# ZOWI_Main_Board_Bluetooth.net
KiCad netlist of a schematic drawn in Altium Designer
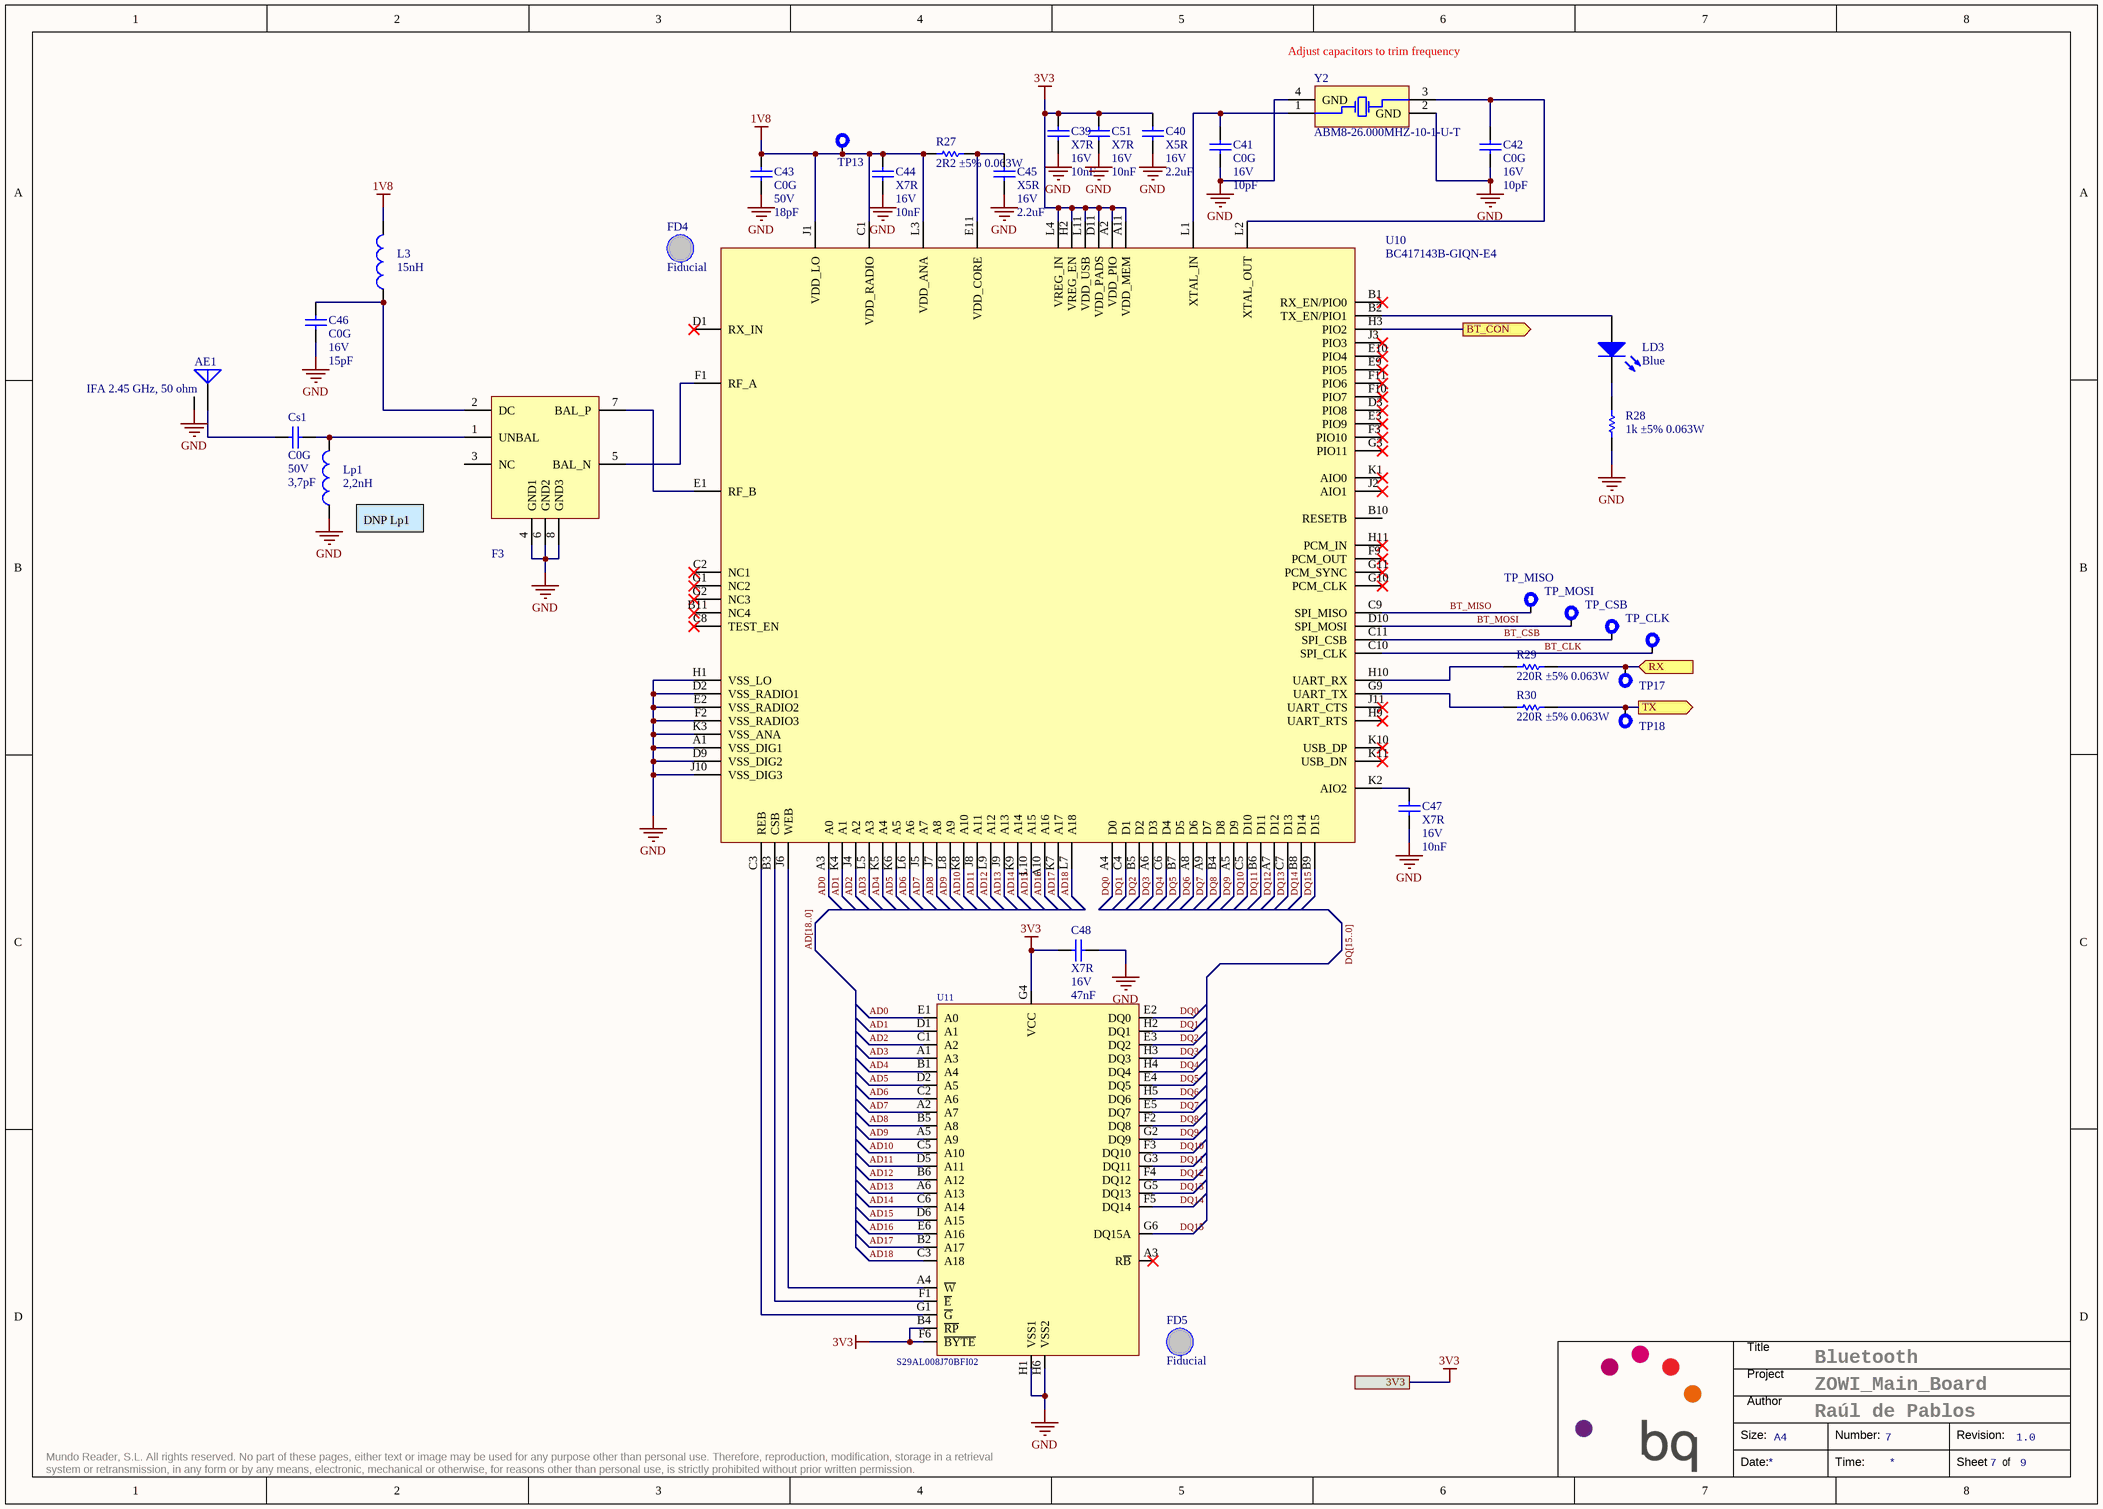
[diagram p0: ZOWI_Main_Board_Bluetooth.SchDoc]

(export (version "E")
  (design (tool "Eeschema 10.0.6"))
  (components
    (comp (ref "AE1")
      (value "~")
      (footprint "IFA_2,45GHZ_50OHM")
      (description "Antenna with Ground")
      (fields (field (name "PART NUMBER") "Microstrip_2.4GHz"))
      (libsource (lib "Antennas") (part "Antenna_WG"))
    )
    (comp (ref "C39")
      (value "Capacitor")
      (footprint "C0402")
      (description "Capacitor SMD")
      (fields
        (field (name "DIELECTRIC") "X7R")
        (field (name "VOLTAGE") "16V")
        (field (name "CAPACITANCE") "10nF")
        (field (name "PART NUMBER") "C0402_10nF_16V_±10%")
        (field (name "TOLERANCE") "±10%")
      )
      (libsource (lib "Pasives_Capacitor_SMD") (part "Capacitor"))
    )
    (comp (ref "C40")
      (value "Capacitor")
      (footprint "C0603")
      (description "Capacitor SMD")
      (fields
        (field (name "DIELECTRIC") "X5R")
        (field (name "VOLTAGE") "16V")
        (field (name "CAPACITANCE") "2.2uF")
        (field (name "PART NUMBER") "C0603_2.2uF_16V_±10%")
        (field (name "TOLERANCE") "±10%")
      )
      (libsource (lib "Pasives_Capacitor_SMD") (part "Capacitor"))
    )
    (comp (ref "C41")
      (value "Capacitor")
      (footprint "C0402")
      (description "Capacitor SMD")
      (fields
        (field (name "DIELECTRIC") "C0G")
        (field (name "VOLTAGE") "16V")
        (field (name "CAPACITANCE") "10pF")
        (field (name "PART NUMBER") "C0402_10pF_16V_±10%")
        (field (name "TOLERANCE") "±10%")
      )
      (libsource (lib "Pasives_Capacitor_SMD") (part "Capacitor"))
    )
    (comp (ref "C42")
      (value "Capacitor")
      (footprint "C0402")
      (description "Capacitor SMD")
      (fields
        (field (name "DIELECTRIC") "C0G")
        (field (name "VOLTAGE") "16V")
        (field (name "CAPACITANCE") "10pF")
        (field (name "PART NUMBER") "C0402_10pF_16V_±10%")
        (field (name "TOLERANCE") "±10%")
      )
      (libsource (lib "Pasives_Capacitor_SMD") (part "Capacitor"))
    )
    (comp (ref "C43")
      (value "Capacitor")
      (footprint "C0402")
      (description "Capacitor SMD")
      (fields
        (field (name "DIELECTRIC") "C0G")
        (field (name "VOLTAGE") "50V")
        (field (name "CAPACITANCE") "18pF")
        (field (name "PART NUMBER") "C0402_18pF_50V_±5%")
        (field (name "TOLERANCE") "±5%")
      )
      (libsource (lib "Pasives_Capacitor_SMD") (part "Capacitor"))
    )
    (comp (ref "C44")
      (value "Capacitor")
      (footprint "C0402")
      (description "Capacitor SMD")
      (fields
        (field (name "DIELECTRIC") "X7R")
        (field (name "VOLTAGE") "16V")
        (field (name "CAPACITANCE") "10nF")
        (field (name "PART NUMBER") "C0402_10nF_16V_±10%")
        (field (name "TOLERANCE") "±10%")
      )
      (libsource (lib "Pasives_Capacitor_SMD") (part "Capacitor"))
    )
    (comp (ref "C45")
      (value "Capacitor")
      (footprint "C0603")
      (description "Capacitor SMD")
      (fields
        (field (name "DIELECTRIC") "X5R")
        (field (name "VOLTAGE") "16V")
        (field (name "CAPACITANCE") "2.2uF")
        (field (name "PART NUMBER") "C0603_2.2uF_16V_±10%")
        (field (name "TOLERANCE") "±10%")
      )
      (libsource (lib "Pasives_Capacitor_SMD") (part "Capacitor"))
    )
    (comp (ref "C46")
      (value "Capacitor")
      (footprint "C0402")
      (description "Capacitor SMD")
      (fields
        (field (name "DIELECTRIC") "C0G")
        (field (name "VOLTAGE") "16V")
        (field (name "CAPACITANCE") "15pF")
        (field (name "PART NUMBER") "C0402_15pF_16V_±10%")
        (field (name "TOLERANCE") "±10%")
      )
      (libsource (lib "Pasives_Capacitor_SMD") (part "Capacitor"))
    )
    (comp (ref "C47")
      (value "Capacitor")
      (footprint "C0402")
      (description "Capacitor SMD")
      (fields
        (field (name "DIELECTRIC") "X7R")
        (field (name "VOLTAGE") "16V")
        (field (name "CAPACITANCE") "10nF")
        (field (name "PART NUMBER") "C0402_10nF_16V_±10%")
        (field (name "TOLERANCE") "±10%")
      )
      (libsource (lib "Pasives_Capacitor_SMD") (part "Capacitor"))
    )
    (comp (ref "C48")
      (value "Capacitor")
      (footprint "C0402")
      (description "Capacitor SMD")
      (fields
        (field (name "DIELECTRIC") "X7R")
        (field (name "VOLTAGE") "16V")
        (field (name "CAPACITANCE") "47nF")
        (field (name "PART NUMBER") "C0402_47nF_16V_±10%")
        (field (name "TOLERANCE") "±10%")
      )
      (libsource (lib "Pasives_Capacitor_SMD") (part "Capacitor"))
    )
    (comp (ref "C51")
      (value "Capacitor")
      (footprint "C0402")
      (description "Capacitor SMD")
      (fields
        (field (name "DIELECTRIC") "X7R")
        (field (name "VOLTAGE") "16V")
        (field (name "CAPACITANCE") "10nF")
        (field (name "PART NUMBER") "C0402_10nF_16V_±10%")
        (field (name "TOLERANCE") "±10%")
      )
      (libsource (lib "Pasives_Capacitor_SMD") (part "Capacitor"))
    )
    (comp (ref "Cs1")
      (value "Capacitor")
      (footprint "C0402")
      (description "Capacitor SMD")
      (fields
        (field (name "DIELECTRIC") "C0G")
        (field (name "VOLTAGE") "50V")
        (field (name "CAPACITANCE") "3,7pF")
        (field (name "PART NUMBER") "C0402_3,7pF_50V_±0.05pF")
        (field (name "TOLERANCE") "±7%")
      )
      (libsource (lib "Pasives_Capacitor_SMD") (part "Capacitor"))
    )
    (comp (ref "F3")
      (value "BP_Filter_Balun")
      (footprint "2450FB15K0005")
      (description "Filter, Band Pass, Balun")
      (fields (field (name "MANUFACTURER") "Johanson Technlogy"))
      (libsource (lib "Pasives_Filter") (part "BP_Filter_Balun"))
    )
    (comp (ref "FD4")
      (value "Fiducial")
      (footprint "Fiducial_Local_0.4mm")
      (description "Fiducial Mark")
      (fields (field (name "PART NUMBER") "Fiducial Local 0.4mm"))
      (libsource (lib "Miscelanea") (part "Fiducial"))
    )
    (comp (ref "FD5")
      (value "Fiducial")
      (footprint "Fiducial_Local_0.4mm")
      (description "Fiducial Mark")
      (fields (field (name "PART NUMBER") "Fiducial Local 0.4mm"))
      (libsource (lib "Miscelanea") (part "Fiducial"))
    )
    (comp (ref "L3")
      (value "~")
      (footprint "L0402")
      (description "Inductor SMD")
      (fields
        (field (name "PART NUMBER") "15nH_0,3A")
        (field (name "L") "15nH")
        (field (name "MANUFACTURER") "Murata")
      )
      (libsource (lib "Pasivos_Inductor_SMD") (part "Inductor"))
    )
    (comp (ref "LD3")
      (value "Blue")
      (footprint "LED0603")
      (description "LED")
      (fields (field (name "PART NUMBER") "LTST-C194TBKT") (field (name "MANUFACTURER") "Lite-On"))
      (libsource (lib "Optoelectronics") (part "LED"))
    )
    (comp (ref "Lp1")
      (value "~")
      (footprint "L0402")
      (description "Inductor SMD")
      (fields
        (field (name "PART NUMBER") "2,2nH_0,9A")
        (field (name "L") "2,2nH")
        (field (name "MANUFACTURER") "Murata")
      )
      (libsource (lib "Pasivos_Inductor_SMD") (part "Inductor"))
    )
    (comp (ref "R27")
      (value "2R2 ±5% 0.063W")
      (footprint "R0402")
      (description "Resistor, SMD")
      (fields (field (name "TOLERANCE") "±5%") (field (name "POWER") "0.063W"))
      (libsource (lib "Pasives_Resistor_SMD") (part "Resistor"))
    )
    (comp (ref "R28")
      (value "1k ±5% 0.063W")
      (footprint "R0402")
      (description "Resistor, SMD")
      (fields (field (name "TOLERANCE") "±5%") (field (name "POWER") "0.063W"))
      (libsource (lib "Pasives_Resistor_SMD") (part "Resistor"))
    )
    (comp (ref "R29")
      (value "220R ±5% 0.063W")
      (footprint "R0402")
      (description "Resistor, SMD")
      (fields (field (name "TOLERANCE") "±5%") (field (name "POWER") "0.063W"))
      (libsource (lib "Pasives_Resistor_SMD") (part "Resistor"))
    )
    (comp (ref "R30")
      (value "220R ±5% 0.063W")
      (footprint "R0402")
      (description "Resistor, SMD")
      (fields (field (name "TOLERANCE") "±5%") (field (name "POWER") "0.063W"))
      (libsource (lib "Pasives_Resistor_SMD") (part "Resistor"))
    )
    (comp (ref "TP13")
      (value "Testpoint")
      (footprint "TP_SMD_1mm")
      (fields (field (name "MANUFACTURER") "Oxley") (field (name "PART NUMBER") "TP_SMD_1mm"))
      (libsource (lib "Miscelanea") (part "Testpoint"))
    )
    (comp (ref "TP17")
      (value "Testpoint")
      (footprint "TP_SMD_1mm")
      (fields (field (name "MANUFACTURER") "Oxley") (field (name "PART NUMBER") "TP_SMD_1mm"))
      (libsource (lib "Miscelanea") (part "Testpoint"))
    )
    (comp (ref "TP18")
      (value "Testpoint")
      (footprint "TP_SMD_1mm")
      (fields (field (name "MANUFACTURER") "Oxley") (field (name "PART NUMBER") "TP_SMD_1mm"))
      (libsource (lib "Miscelanea") (part "Testpoint"))
    )
    (comp (ref "TP_CLK")
      (value "Testpoint")
      (footprint "TP_SMD_1mm")
      (fields (field (name "MANUFACTURER") "Oxley") (field (name "PART NUMBER") "TP_SMD_1mm"))
      (libsource (lib "Miscelanea") (part "Testpoint"))
    )
    (comp (ref "TP_CSB")
      (value "Testpoint")
      (footprint "TP_SMD_1mm")
      (fields (field (name "MANUFACTURER") "Oxley") (field (name "PART NUMBER") "TP_SMD_1mm"))
      (libsource (lib "Miscelanea") (part "Testpoint"))
    )
    (comp (ref "TP_MISO")
      (value "Testpoint")
      (footprint "TP_SMD_1mm")
      (fields (field (name "MANUFACTURER") "Oxley") (field (name "PART NUMBER") "TP_SMD_1mm"))
      (libsource (lib "Miscelanea") (part "Testpoint"))
    )
    (comp (ref "TP_MOSI")
      (value "Testpoint")
      (footprint "TP_SMD_1mm")
      (fields (field (name "MANUFACTURER") "Oxley") (field (name "PART NUMBER") "TP_SMD_1mm"))
      (libsource (lib "Miscelanea") (part "Testpoint"))
    )
    (comp (ref "U10")
      (value "BC417143B-GIQN-E4")
      (footprint "TFBGA96P8X8")
      (description "Bluetooth Modem, 2.4-GHz Bluetooth SoC")
      (fields (field (name "PART NUMBER") "BlueCore4-EXT") (field (name "MANUFACTURER") "CSR"))
      (libsource (lib "Transceiver") (part "BC417143B"))
    )
    (comp (ref "U11")
      (value "S29AL008J70BFI02")
      (footprint "TFBGA48P6X8")
      (description "Memory NOR Flash 8-Mbit 3 V supply")
      (fields (field (name "PART NUMBER") "M29W800DT") (field (name "MANUFACTURER") "Spansion"))
      (libsource (lib "Memory_NOR") (part "M29W800DT"))
    )
    (comp (ref "Y2")
      (value "ABM8-26.000MHZ-10-1-U-T")
      (footprint "XTAL 3.2x2.5")
      (description "Crystal 4 pin")
      (fields (field (name "PART NUMBER") "403C11A 26MHz") (field (name "TOLERANCE") "±10ppm"))
      (libsource (lib "Frequency") (part "Crystal 4 pin"))
    )
  )
  (nets
    (net (code "1") (name "/AD0") (class "Default")
      (node (ref "U10") (pin "A3") (pinfunction "A0_A3") (pintype "passive"))
      (node (ref "U11") (pin "E1") (pinfunction "A0_E1") (pintype "passive"))
    )
    (net (code "2") (name "/AD1") (class "Default")
      (node (ref "U10") (pin "K4") (pinfunction "A1_K4") (pintype "passive"))
      (node (ref "U11") (pin "D1") (pinfunction "A1_D1") (pintype "passive"))
    )
    (net (code "3") (name "/AD2") (class "Default")
      (node (ref "U10") (pin "J4") (pinfunction "A2_J4") (pintype "passive"))
      (node (ref "U11") (pin "C1") (pinfunction "A2_C1") (pintype "passive"))
    )
    (net (code "4") (name "/AD3") (class "Default")
      (node (ref "U10") (pin "L5") (pinfunction "A3_L5") (pintype "passive"))
      (node (ref "U11") (pin "A1") (pinfunction "A3_A1") (pintype "passive"))
    )
    (net (code "5") (name "/AD4") (class "Default")
      (node (ref "U10") (pin "K5") (pinfunction "A4_K5") (pintype "passive"))
      (node (ref "U11") (pin "B1") (pinfunction "A4_B1") (pintype "passive"))
    )
    (net (code "6") (name "/AD5") (class "Default")
      (node (ref "U10") (pin "K6") (pinfunction "A5_K6") (pintype "passive"))
      (node (ref "U11") (pin "D2") (pinfunction "A5_D2") (pintype "passive"))
    )
    (net (code "7") (name "/AD6") (class "Default")
      (node (ref "U10") (pin "L6") (pinfunction "A6_L6") (pintype "passive"))
      (node (ref "U11") (pin "C2") (pinfunction "A6_C2") (pintype "passive"))
    )
    (net (code "8") (name "/AD7") (class "Default")
      (node (ref "U10") (pin "J5") (pinfunction "A7_J5") (pintype "passive"))
      (node (ref "U11") (pin "A2") (pinfunction "A7_A2") (pintype "passive"))
    )
    (net (code "9") (name "/AD8") (class "Default")
      (node (ref "U10") (pin "J7") (pinfunction "A8_J7") (pintype "passive"))
      (node (ref "U11") (pin "B5") (pinfunction "A8_B5") (pintype "passive"))
    )
    (net (code "10") (name "/AD9") (class "Default")
      (node (ref "U10") (pin "L8") (pinfunction "A9_L8") (pintype "passive"))
      (node (ref "U11") (pin "A5") (pinfunction "A9_A5") (pintype "passive"))
    )
    (net (code "11") (name "/AD10") (class "Default")
      (node (ref "U10") (pin "K8") (pinfunction "A10_K8") (pintype "passive"))
      (node (ref "U11") (pin "C5") (pinfunction "A10_C5") (pintype "passive"))
    )
    (net (code "12") (name "/AD11") (class "Default")
      (node (ref "U10") (pin "J8") (pinfunction "A11_J8") (pintype "passive"))
      (node (ref "U11") (pin "D5") (pinfunction "A11_D5") (pintype "passive"))
    )
    (net (code "13") (name "/AD12") (class "Default")
      (node (ref "U10") (pin "L9") (pinfunction "A12_L9") (pintype "passive"))
      (node (ref "U11") (pin "B6") (pinfunction "A12_B6") (pintype "passive"))
    )
    (net (code "14") (name "/AD13") (class "Default")
      (node (ref "U10") (pin "J9") (pinfunction "A13_J9") (pintype "passive"))
      (node (ref "U11") (pin "A6") (pinfunction "A13_A6") (pintype "passive"))
    )
    (net (code "15") (name "/AD14") (class "Default")
      (node (ref "U10") (pin "K9") (pinfunction "A14_K9") (pintype "passive"))
      (node (ref "U11") (pin "C6") (pinfunction "A14_C6") (pintype "passive"))
    )
    (net (code "16") (name "/AD15") (class "Default")
      (node (ref "U10") (pin "L10") (pinfunction "A15_L10") (pintype "passive"))
      (node (ref "U11") (pin "D6") (pinfunction "A15_D6") (pintype "passive"))
    )
    (net (code "17") (name "/AD16") (class "Default")
      (node (ref "U10") (pin "A10") (pinfunction "A16_A10") (pintype "passive"))
      (node (ref "U11") (pin "E6") (pinfunction "A16_E6") (pintype "passive"))
    )
    (net (code "18") (name "/AD17") (class "Default")
      (node (ref "U10") (pin "K7") (pinfunction "A17_K7") (pintype "passive"))
      (node (ref "U11") (pin "B2") (pinfunction "A17_B2") (pintype "passive"))
    )
    (net (code "19") (name "/AD18") (class "Default")
      (node (ref "U10") (pin "L7") (pinfunction "A18_L7") (pintype "passive"))
      (node (ref "U11") (pin "C3") (pinfunction "A18_C3") (pintype "passive"))
    )
    (net (code "21") (name "/BT_CLK") (class "Default")
      (node (ref "TP_CLK") (pin "1") (pinfunction "1_1") (pintype "passive"))
      (node (ref "U10") (pin "C10") (pinfunction "SPI_CLK_C10") (pintype "passive"))
    )
    (net (code "22") (name "/BT_CON") (class "Default")
      (node (ref "U10") (pin "H3") (pinfunction "PIO2_H3") (pintype "passive"))
    )
    (net (code "23") (name "/BT_CSB") (class "Default")
      (node (ref "TP_CSB") (pin "1") (pinfunction "1_1") (pintype "passive"))
      (node (ref "U10") (pin "C11") (pinfunction "SPI_CSB_C11") (pintype "passive"))
    )
    (net (code "24") (name "/BT_MISO") (class "Default")
      (node (ref "TP_MISO") (pin "1") (pinfunction "1_1") (pintype "passive"))
      (node (ref "U10") (pin "C9") (pinfunction "SPI_MISO_C9") (pintype "passive"))
    )
    (net (code "25") (name "/BT_MOSI") (class "Default")
      (node (ref "TP_MOSI") (pin "1") (pinfunction "1_1") (pintype "passive"))
      (node (ref "U10") (pin "D10") (pinfunction "SPI_MOSI_D10") (pintype "passive"))
    )
    (net (code "26") (name "/DQ0") (class "Default")
      (node (ref "U10") (pin "A4") (pinfunction "D0_A4") (pintype "passive"))
      (node (ref "U11") (pin "E2") (pinfunction "DQ0_E2") (pintype "passive"))
    )
    (net (code "27") (name "/DQ1") (class "Default")
      (node (ref "U10") (pin "C4") (pinfunction "D1_C4") (pintype "passive"))
      (node (ref "U11") (pin "H2") (pinfunction "DQ1_H2") (pintype "passive"))
    )
    (net (code "28") (name "/DQ2") (class "Default")
      (node (ref "U10") (pin "B5") (pinfunction "D2_B5") (pintype "passive"))
      (node (ref "U11") (pin "E3") (pinfunction "DQ2_E3") (pintype "passive"))
    )
    (net (code "29") (name "/DQ3") (class "Default")
      (node (ref "U10") (pin "A6") (pinfunction "D3_A6") (pintype "passive"))
      (node (ref "U11") (pin "H3") (pinfunction "DQ3_H3") (pintype "passive"))
    )
    (net (code "30") (name "/DQ4") (class "Default")
      (node (ref "U10") (pin "C6") (pinfunction "D4_C6") (pintype "passive"))
      (node (ref "U11") (pin "H4") (pinfunction "DQ4_H4") (pintype "passive"))
    )
    (net (code "31") (name "/DQ5") (class "Default")
      (node (ref "U10") (pin "B7") (pinfunction "D5_B7") (pintype "passive"))
      (node (ref "U11") (pin "E4") (pinfunction "DQ5_E4") (pintype "passive"))
    )
    (net (code "32") (name "/DQ6") (class "Default")
      (node (ref "U10") (pin "A8") (pinfunction "D6_A8") (pintype "passive"))
      (node (ref "U11") (pin "H5") (pinfunction "DQ6_H5") (pintype "passive"))
    )
    (net (code "33") (name "/DQ7") (class "Default")
      (node (ref "U10") (pin "A9") (pinfunction "D7_A9") (pintype "passive"))
      (node (ref "U11") (pin "E5") (pinfunction "DQ7_E5") (pintype "passive"))
    )
    (net (code "34") (name "/DQ8") (class "Default")
      (node (ref "U10") (pin "B4") (pinfunction "D8_B4") (pintype "passive"))
      (node (ref "U11") (pin "F2") (pinfunction "DQ8_F2") (pintype "passive"))
    )
    (net (code "35") (name "/DQ9") (class "Default")
      (node (ref "U10") (pin "A5") (pinfunction "D9_A5") (pintype "passive"))
      (node (ref "U11") (pin "G2") (pinfunction "DQ9_G2") (pintype "passive"))
    )
    (net (code "36") (name "/DQ10") (class "Default")
      (node (ref "U10") (pin "C5") (pinfunction "D10_C5") (pintype "passive"))
      (node (ref "U11") (pin "F3") (pinfunction "DQ10_F3") (pintype "passive"))
    )
    (net (code "37") (name "/DQ11") (class "Default")
      (node (ref "U10") (pin "B6") (pinfunction "D11_B6") (pintype "passive"))
      (node (ref "U11") (pin "G3") (pinfunction "DQ11_G3") (pintype "passive"))
    )
    (net (code "38") (name "/DQ12") (class "Default")
      (node (ref "U10") (pin "A7") (pinfunction "D12_A7") (pintype "passive"))
      (node (ref "U11") (pin "F4") (pinfunction "DQ12_F4") (pintype "passive"))
    )
    (net (code "39") (name "/DQ13") (class "Default")
      (node (ref "U10") (pin "C7") (pinfunction "D13_C7") (pintype "passive"))
      (node (ref "U11") (pin "G5") (pinfunction "DQ13_G5") (pintype "passive"))
    )
    (net (code "40") (name "/DQ14") (class "Default")
      (node (ref "U10") (pin "B8") (pinfunction "D14_B8") (pintype "passive"))
      (node (ref "U11") (pin "F5") (pinfunction "DQ14_F5") (pintype "passive"))
    )
    (net (code "41") (name "/DQ15") (class "Default")
      (node (ref "U10") (pin "B9") (pinfunction "D15_B9") (pintype "passive"))
      (node (ref "U11") (pin "G6") (pinfunction "DQ15A_G6") (pintype "passive"))
    )
    (net (code "43") (name "/RX") (class "Default")
      (node (ref "R29") (pin "2") (pinfunction "2_2") (pintype "passive"))
      (node (ref "TP17") (pin "1") (pinfunction "1_1") (pintype "passive"))
    )
    (net (code "44") (name "/TX") (class "Default")
      (node (ref "R30") (pin "2") (pinfunction "2_2") (pintype "passive"))
      (node (ref "TP18") (pin "1") (pinfunction "1_1") (pintype "passive"))
    )
    (net (code "45") (name "1V8") (class "Default")
      (node (ref "C43") (pin "2") (pinfunction "2_2") (pintype "passive"))
      (node (ref "C44") (pin "2") (pinfunction "2_2") (pintype "passive"))
      (node (ref "L3") (pin "2") (pinfunction "2_2") (pintype "passive"))
      (node (ref "R27") (pin "2") (pinfunction "2_2") (pintype "passive"))
      (node (ref "TP13") (pin "1") (pinfunction "1_1") (pintype "passive"))
      (node (ref "U10") (pin "C1") (pinfunction "VDD_RADIO_C1") (pintype "passive"))
      (node (ref "U10") (pin "J1") (pinfunction "VDD_LO_J1") (pintype "passive"))
      (node (ref "U10") (pin "L3") (pinfunction "VDD_ANA_L3") (pintype "passive"))
    )
    (net (code "46") (name "3V3") (class "Default")
      (node (ref "C39") (pin "2") (pinfunction "2_2") (pintype "passive"))
      (node (ref "C40") (pin "2") (pinfunction "2_2") (pintype "passive"))
      (node (ref "C48") (pin "1") (pinfunction "1_1") (pintype "passive"))
      (node (ref "C51") (pin "2") (pinfunction "2_2") (pintype "passive"))
      (node (ref "U10") (pin "A11") (pinfunction "VDD_MEM_A11") (pintype "passive"))
      (node (ref "U10") (pin "A2") (pinfunction "VDD_PIO_A2") (pintype "passive"))
      (node (ref "U10") (pin "D11") (pinfunction "VDD_PADS_D11") (pintype "passive"))
      (node (ref "U10") (pin "H2") (pinfunction "VREG_EN_H2") (pintype "passive"))
      (node (ref "U10") (pin "L11") (pinfunction "VDD_USB_L11") (pintype "passive"))
      (node (ref "U10") (pin "L4") (pinfunction "VREG_IN_L4") (pintype "passive"))
      (node (ref "U11") (pin "B4") (pinfunction "~{RP}_B4") (pintype "passive"))
      (node (ref "U11") (pin "F6") (pinfunction "~{BYTE}_F6") (pintype "passive"))
      (node (ref "U11") (pin "G4") (pinfunction "VCC_G4") (pintype "passive"))
    )
    (net (code "47") (name "GND") (class "Default")
      (node (ref "AE1") (pin "GND") (pinfunction "GND_GND") (pintype "passive"))
      (node (ref "C39") (pin "1") (pinfunction "1_1") (pintype "passive"))
      (node (ref "C40") (pin "1") (pinfunction "1_1") (pintype "passive"))
      (node (ref "C41") (pin "1") (pinfunction "1_1") (pintype "passive"))
      (node (ref "C42") (pin "1") (pinfunction "1_1") (pintype "passive"))
      (node (ref "C43") (pin "1") (pinfunction "1_1") (pintype "passive"))
      (node (ref "C44") (pin "1") (pinfunction "1_1") (pintype "passive"))
      (node (ref "C45") (pin "1") (pinfunction "1_1") (pintype "passive"))
      (node (ref "C46") (pin "1") (pinfunction "1_1") (pintype "passive"))
      (node (ref "C47") (pin "1") (pinfunction "1_1") (pintype "passive"))
      (node (ref "C48") (pin "2") (pinfunction "2_2") (pintype "passive"))
      (node (ref "C51") (pin "1") (pinfunction "1_1") (pintype "passive"))
      (node (ref "F3") (pin "4") (pinfunction "GND1_4") (pintype "power_in"))
      (node (ref "F3") (pin "6") (pinfunction "GND2_6") (pintype "power_in"))
      (node (ref "F3") (pin "8") (pinfunction "GND3_8") (pintype "power_in"))
      (node (ref "Lp1") (pin "1") (pinfunction "1_1") (pintype "passive"))
      (node (ref "R28") (pin "1") (pinfunction "1_1") (pintype "passive"))
      (node (ref "U10") (pin "A1") (pinfunction "VSS_DIG1_A1") (pintype "passive"))
      (node (ref "U10") (pin "D2") (pinfunction "VSS_RADIO1_D2") (pintype "passive"))
      (node (ref "U10") (pin "D9") (pinfunction "VSS_DIG2_D9") (pintype "passive"))
      (node (ref "U10") (pin "E2") (pinfunction "VSS_RADIO2_E2") (pintype "passive"))
      (node (ref "U10") (pin "F2") (pinfunction "VSS_RADIO3_F2") (pintype "passive"))
      (node (ref "U10") (pin "H1") (pinfunction "VSS_LO_H1") (pintype "passive"))
      (node (ref "U10") (pin "J10") (pinfunction "VSS_DIG3_J10") (pintype "passive"))
      (node (ref "U10") (pin "K3") (pinfunction "VSS_ANA_K3") (pintype "passive"))
      (node (ref "U11") (pin "H1") (pinfunction "VSS1_H1") (pintype "passive"))
      (node (ref "U11") (pin "H6") (pinfunction "VSS2_H6") (pintype "passive"))
      (node (ref "Y2") (pin "2") (pinfunction "GND_2") (pintype "passive"))
      (node (ref "Y2") (pin "4") (pinfunction "GND_4") (pintype "passive"))
    )
    (net (code "48") (name "Net-(AE1-PadFEED)") (class "Default")
      (node (ref "AE1") (pin "FEED") (pinfunction "FEED_FEED") (pintype "passive"))
      (node (ref "Cs1") (pin "1") (pinfunction "1_1") (pintype "passive"))
    )
    (net (code "49") (name "Net-(F3-BAL_N)") (class "Default")
      (node (ref "F3") (pin "5") (pinfunction "BAL_N_5") (pintype "passive"))
      (node (ref "U10") (pin "F1") (pinfunction "RF_A_F1") (pintype "passive"))
    )
    (net (code "50") (name "Net-(F3-BAL_P)") (class "Default")
      (node (ref "F3") (pin "7") (pinfunction "BAL_P_7") (pintype "passive"))
      (node (ref "U10") (pin "E1") (pinfunction "RF_B_E1") (pintype "passive"))
    )
    (net (code "51") (name "Net-(F3-DC)") (class "Default")
      (node (ref "C46") (pin "2") (pinfunction "2_2") (pintype "passive"))
      (node (ref "F3") (pin "2") (pinfunction "DC_2") (pintype "passive"))
      (node (ref "L3") (pin "1") (pinfunction "1_1") (pintype "passive"))
    )
    (net (code "52") (name "Net-(F3-UNBAL)") (class "Default")
      (node (ref "Cs1") (pin "2") (pinfunction "2_2") (pintype "passive"))
      (node (ref "F3") (pin "1") (pinfunction "UNBAL_1") (pintype "passive"))
      (node (ref "Lp1") (pin "2") (pinfunction "2_2") (pintype "passive"))
    )
    (net (code "53") (name "Net-(LD3-PadK)") (class "Default")
      (node (ref "LD3") (pin "K") (pinfunction "K_K") (pintype "passive"))
      (node (ref "R28") (pin "2") (pinfunction "2_2") (pintype "passive"))
    )
    (net (code "54") (name "Net-(U10-AIO2)") (class "Default")
      (node (ref "C47") (pin "2") (pinfunction "2_2") (pintype "passive"))
      (node (ref "U10") (pin "K2") (pinfunction "AIO2_K2") (pintype "passive"))
    )
    (net (code "55") (name "Net-(U10-CSB)") (class "Default")
      (node (ref "U10") (pin "B3") (pinfunction "CSB_B3") (pintype "passive"))
      (node (ref "U11") (pin "F1") (pinfunction "~{E}_F1") (pintype "passive"))
    )
    (net (code "56") (name "Net-(U10-REB)") (class "Default")
      (node (ref "U10") (pin "C3") (pinfunction "REB_C3") (pintype "passive"))
      (node (ref "U11") (pin "G1") (pinfunction "~{G}_G1") (pintype "passive"))
    )
    (net (code "57") (name "Net-(U10-TX_EN{slash}PIO1)") (class "Default")
      (node (ref "LD3") (pin "A") (pinfunction "A_A") (pintype "passive"))
      (node (ref "U10") (pin "B2") (pinfunction "TX_EN/PIO1_B2") (pintype "passive"))
    )
    (net (code "58") (name "Net-(U10-UART_RX)") (class "Default")
      (node (ref "R29") (pin "1") (pinfunction "1_1") (pintype "passive"))
      (node (ref "U10") (pin "H10") (pinfunction "UART_RX_H10") (pintype "passive"))
    )
    (net (code "59") (name "Net-(U10-UART_TX)") (class "Default")
      (node (ref "R30") (pin "1") (pinfunction "1_1") (pintype "passive"))
      (node (ref "U10") (pin "G9") (pinfunction "UART_TX_G9") (pintype "passive"))
    )
    (net (code "60") (name "Net-(U10-VDD_CORE)") (class "Default")
      (node (ref "C45") (pin "2") (pinfunction "2_2") (pintype "passive"))
      (node (ref "R27") (pin "1") (pinfunction "1_1") (pintype "passive"))
      (node (ref "U10") (pin "E11") (pinfunction "VDD_CORE_E11") (pintype "passive"))
    )
    (net (code "61") (name "Net-(U10-WEB)") (class "Default")
      (node (ref "U10") (pin "J6") (pinfunction "WEB_J6") (pintype "passive"))
      (node (ref "U11") (pin "A4") (pinfunction "~{W}_A4") (pintype "passive"))
    )
    (net (code "62") (name "Net-(U10-XTAL_IN)") (class "Default")
      (node (ref "C41") (pin "2") (pinfunction "2_2") (pintype "passive"))
      (node (ref "U10") (pin "L1") (pinfunction "XTAL_IN_L1") (pintype "passive"))
      (node (ref "Y2") (pin "1") (pinfunction "OSC1_1") (pintype "passive"))
    )
    (net (code "63") (name "Net-(U10-XTAL_OUT)") (class "Default")
      (node (ref "C42") (pin "2") (pinfunction "2_2") (pintype "passive"))
      (node (ref "U10") (pin "L2") (pinfunction "XTAL_OUT_L2") (pintype "passive"))
      (node (ref "Y2") (pin "3") (pinfunction "OSC2_3") (pintype "passive"))
    )
    (net (code "64") (name "unconnected-(F3-NC-Pad3)") (class "Default")
      (node (ref "F3") (pin "3") (pinfunction "NC_3") (pintype "passive"))
    )
    (net (code "65") (name "unconnected-(U10-AIO0-PadK1)") (class "Default")
      (node (ref "U10") (pin "K1") (pinfunction "AIO0_K1") (pintype "passive+no_connect"))
    )
    (net (code "66") (name "unconnected-(U10-AIO1-PadJ2)") (class "Default")
      (node (ref "U10") (pin "J2") (pinfunction "AIO1_J2") (pintype "passive+no_connect"))
    )
    (net (code "67") (name "unconnected-(U10-NC1-PadC2)") (class "Default")
      (node (ref "U10") (pin "C2") (pinfunction "NC1_C2") (pintype "passive+no_connect"))
    )
    (net (code "68") (name "unconnected-(U10-NC2-PadG1)") (class "Default")
      (node (ref "U10") (pin "G1") (pinfunction "NC2_G1") (pintype "passive+no_connect"))
    )
    (net (code "69") (name "unconnected-(U10-NC3-PadG2)") (class "Default")
      (node (ref "U10") (pin "G2") (pinfunction "NC3_G2") (pintype "passive+no_connect"))
    )
    (net (code "70") (name "unconnected-(U10-NC4-PadB11)") (class "Default")
      (node (ref "U10") (pin "B11") (pinfunction "NC4_B11") (pintype "passive+no_connect"))
    )
    (net (code "71") (name "unconnected-(U10-PCM_CLK-PadG10)") (class "Default")
      (node (ref "U10") (pin "G10") (pinfunction "PCM_CLK_G10") (pintype "passive+no_connect"))
    )
    (net (code "72") (name "unconnected-(U10-PCM_IN-PadH11)") (class "Default")
      (node (ref "U10") (pin "H11") (pinfunction "PCM_IN_H11") (pintype "passive+no_connect"))
    )
    (net (code "73") (name "unconnected-(U10-PCM_OUT-PadF9)") (class "Default")
      (node (ref "U10") (pin "F9") (pinfunction "PCM_OUT_F9") (pintype "passive+no_connect"))
    )
    (net (code "74") (name "unconnected-(U10-PCM_SYNC-PadG11)") (class "Default")
      (node (ref "U10") (pin "G11") (pinfunction "PCM_SYNC_G11") (pintype "passive+no_connect"))
    )
    (net (code "75") (name "unconnected-(U10-PIO3-PadJ3)") (class "Default")
      (node (ref "U10") (pin "J3") (pinfunction "PIO3_J3") (pintype "passive+no_connect"))
    )
    (net (code "76") (name "unconnected-(U10-PIO4-PadE10)") (class "Default")
      (node (ref "U10") (pin "E10") (pinfunction "PIO4_E10") (pintype "passive+no_connect"))
    )
    (net (code "77") (name "unconnected-(U10-PIO5-PadE9)") (class "Default")
      (node (ref "U10") (pin "E9") (pinfunction "PIO5_E9") (pintype "passive+no_connect"))
    )
    (net (code "78") (name "unconnected-(U10-PIO6-PadF11)") (class "Default")
      (node (ref "U10") (pin "F11") (pinfunction "PIO6_F11") (pintype "passive+no_connect"))
    )
    (net (code "79") (name "unconnected-(U10-PIO7-PadF10)") (class "Default")
      (node (ref "U10") (pin "F10") (pinfunction "PIO7_F10") (pintype "passive+no_connect"))
    )
    (net (code "80") (name "unconnected-(U10-PIO8-PadD3)") (class "Default")
      (node (ref "U10") (pin "D3") (pinfunction "PIO8_D3") (pintype "passive+no_connect"))
    )
    (net (code "81") (name "unconnected-(U10-PIO9-PadE3)") (class "Default")
      (node (ref "U10") (pin "E3") (pinfunction "PIO9_E3") (pintype "passive+no_connect"))
    )
    (net (code "82") (name "unconnected-(U10-PIO10-PadF3)") (class "Default")
      (node (ref "U10") (pin "F3") (pinfunction "PIO10_F3") (pintype "passive+no_connect"))
    )
    (net (code "83") (name "unconnected-(U10-PIO11-PadG3)") (class "Default")
      (node (ref "U10") (pin "G3") (pinfunction "PIO11_G3") (pintype "passive+no_connect"))
    )
    (net (code "84") (name "unconnected-(U10-RESETB-PadB10)") (class "Default")
      (node (ref "U10") (pin "B10") (pinfunction "RESETB_B10") (pintype "passive"))
    )
    (net (code "85") (name "unconnected-(U10-RX_EN{slash}PIO0-PadB1)") (class "Default")
      (node (ref "U10") (pin "B1") (pinfunction "RX_EN/PIO0_B1") (pintype "passive+no_connect"))
    )
    (net (code "86") (name "unconnected-(U10-RX_IN-PadD1)") (class "Default")
      (node (ref "U10") (pin "D1") (pinfunction "RX_IN_D1") (pintype "passive+no_connect"))
    )
    (net (code "87") (name "unconnected-(U10-TEST_EN-PadC8)") (class "Default")
      (node (ref "U10") (pin "C8") (pinfunction "TEST_EN_C8") (pintype "passive+no_connect"))
    )
    (net (code "88") (name "unconnected-(U10-UART_CTS-PadJ11)") (class "Default")
      (node (ref "U10") (pin "J11") (pinfunction "UART_CTS_J11") (pintype "passive+no_connect"))
    )
    (net (code "89") (name "unconnected-(U10-UART_RTS-PadH9)") (class "Default")
      (node (ref "U10") (pin "H9") (pinfunction "UART_RTS_H9") (pintype "passive+no_connect"))
    )
    (net (code "90") (name "unconnected-(U10-USB_DN-PadK11)") (class "Default")
      (node (ref "U10") (pin "K11") (pinfunction "USB_DN_K11") (pintype "passive+no_connect"))
    )
    (net (code "91") (name "unconnected-(U10-USB_DP-PadK10)") (class "Default")
      (node (ref "U10") (pin "K10") (pinfunction "USB_DP_K10") (pintype "passive+no_connect"))
    )
    (net (code "92") (name "unconnected-(U11-R~{B}-PadA3)") (class "Default")
      (node (ref "U11") (pin "A3") (pinfunction "R~{B}_A3") (pintype "passive+no_connect"))
    )
  )
)
